# RelaySchema.net
KiCad netlist of a schematic drawn in Altium Designer
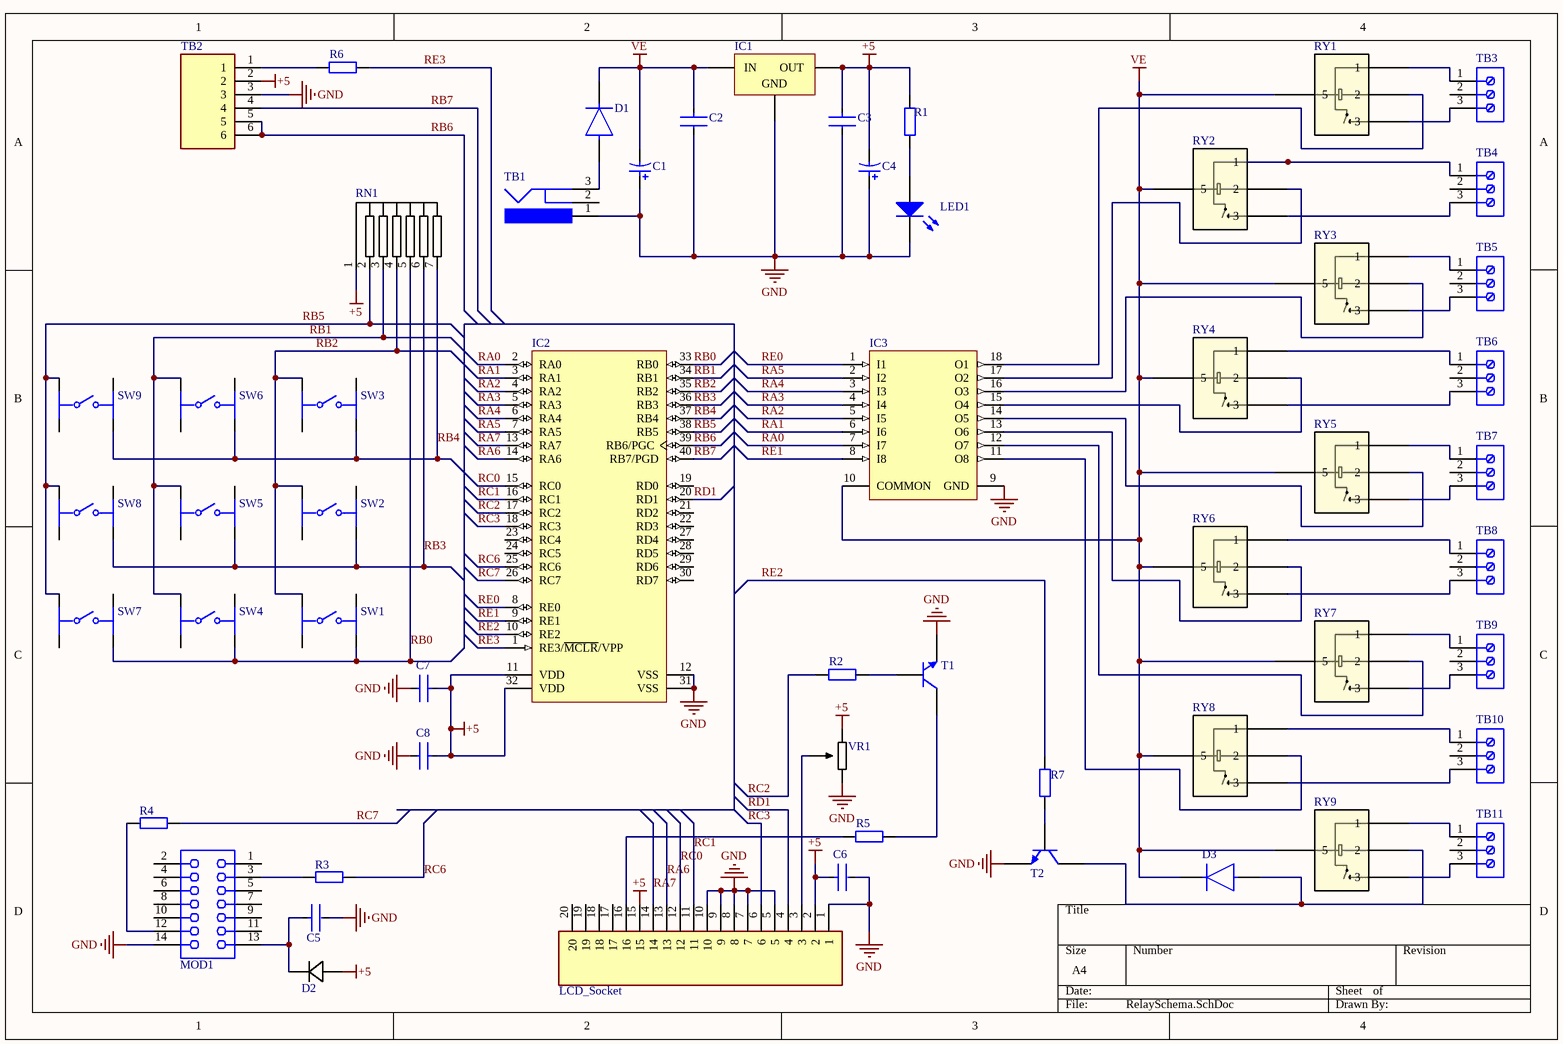
[diagram p0: RelaySchema.SchDoc]

(export (version "E")
  (design (tool "Eeschema 10.0.6"))
  (components
    (comp (ref "C1")
      (value "ECA-1HM221")
      (footprint "CAPPR65-500-1250X1000X1350")
      (description "Aluminum Electrolytic Capacitor, 220 uF, +/- 20%, 50 V, -40 to 85 degC, 2-Pin THD, RoHS, Bulk")
      (libsource (lib "Altium Content Vault") (part "CAP-P-2"))
    )
    (comp (ref "C2")
      (value "SR205C104KAR")
      (footprint "FP-SR20-MFG")
      (description "CAP CER 0.1UF 50V X7R RADIAL")
      (fields (field (name "VOLTAGE") "50V") (field (name "TOLERANCE") "10%"))
      (libsource (lib "Altium Content Vault") (part "11868f565c42a9108669ba33697ecf6"))
    )
    (comp (ref "C3")
      (value "SR205C104KAR")
      (footprint "FP-SR20-MFG")
      (description "CAP CER 0.1UF 50V X7R RADIAL")
      (fields (field (name "VOLTAGE") "50V") (field (name "TOLERANCE") "10%"))
      (libsource (lib "Altium Content Vault") (part "11868f565c42a9108669ba33697ecf6"))
    )
    (comp (ref "C4")
      (value "ECA1HM101")
      (footprint "CAPPR65-350-1150X800X1250")
      (description "Aluminum Electrolytic Capacitor, 100 uF, +/- 20%, 50 V, -40 to 85 degC, 2-Pin THD, RoHS, Bulk")
      (fields (field (name "MANUFACTURER") "Panasonic") (field (name "VOLTAGE") "50V"))
      (libsource (lib "Altium Content Vault") (part "CAP-P-2"))
    )
    (comp (ref "C5")
      (value "SR205C104KAR")
      (footprint "FP-SR20-MFG")
      (description "CAP CER 0.1UF 50V X7R RADIAL")
      (fields (field (name "VOLTAGE") "50V") (field (name "TOLERANCE") "10%"))
      (libsource (lib "Altium Content Vault") (part "11868f565c42a9108669ba33697ecf6"))
    )
    (comp (ref "C6")
      (value "SR205C104KAR")
      (footprint "FP-SR20-MFG")
      (description "CAP CER 0.1UF 50V X7R RADIAL")
      (fields (field (name "VOLTAGE") "50V") (field (name "TOLERANCE") "10%"))
      (libsource (lib "Altium Content Vault") (part "11868f565c42a9108669ba33697ecf6"))
    )
    (comp (ref "C7")
      (value "SR205C104KAR")
      (footprint "FP-SR20-MFG")
      (description "CAP CER 0.1UF 50V X7R RADIAL")
      (fields (field (name "VOLTAGE") "50V") (field (name "TOLERANCE") "10%"))
      (libsource (lib "Altium Content Vault") (part "11868f565c42a9108669ba33697ecf6"))
    )
    (comp (ref "C8")
      (value "SR205C104KAR")
      (footprint "FP-SR20-MFG")
      (description "CAP CER 0.1UF 50V X7R RADIAL")
      (fields (field (name "VOLTAGE") "50V") (field (name "TOLERANCE") "10%"))
      (libsource (lib "Altium Content Vault") (part "11868f565c42a9108669ba33697ecf6"))
    )
    (comp (ref "D1")
      (value "1N4007")
      (footprint "FP-1N4007-MFG")
      (description "Rectifier diode 1000 V 1 A DO-41, ,")
      (fields
        (field (name "MANUFACTURER") "Diotec")
        (field (name "OCTOPART") "https://octopart.com/1n4007-diotec-4040411")
      )
      (libsource (lib "Altium Content Vault") (part "d7152d700b627762746794eb795d46e"))
    )
    (comp (ref "D2")
      (value "BAT43")
      (footprint "DO-35_STM")
      (description "No Description Available")
      (fields (field (name "COPYRIGHT") "Copyright (C) 2018 Accelerated Designs. All rights reserved"))
      (libsource (lib "2021-03-09_13-20-37") (part "BAT43"))
    )
    (comp (ref "D3")
      (value "1N4007")
      (footprint "FP-1N4007-MFG")
      (description "Rectifier diode 1000 V 1 A DO-41, ,")
      (fields
        (field (name "MANUFACTURER") "Diotec")
        (field (name "OCTOPART") "https://octopart.com/1n4007-diotec-4040411")
      )
      (libsource (lib "Altium Content Vault") (part "d7152d700b627762746794eb795d46e"))
    )
    (comp (ref "IC1")
      (value "MC7805CTG")
      (footprint "ONSC-TO-220-3-221AB-01")
      (description "Positive Voltage Regulator, 1 A, 5 V, 0 to 125 degC, 3-Pin TO-220, RoHS, Tube")
      (fields (field (name "MANUFACTURER") "ON Semiconductor"))
      (libsource (lib "Altium Content Vault") (part "ONSC-MC7805CTG-TO-220-3"))
    )
    (comp (ref "IC2")
      (value "PIC18F45K22-E/P")
      (footprint "MCHP-PDIP-P40")
      (fields (field (name "MANUFACTURER") "Microchip"))
      (libsource (lib "Altium Content Vault") (part "MCHP-PIC18F4XK22-PDIP-40"))
    )
    (comp (ref "IC3")
      (value "ULN2803A")
      (footprint "STM-DIP-18")
      (description "Eight Darlington Arrays, 50 V, 2.25 W, 500 mA, 18-Pin DIP, RoHS, Tube")
      (fields (field (name "MANUFACTURER") "STMicroelectronics"))
      (libsource (lib "Altium Content Vault") (part "TOSH-ULN2803_04-DIP-18"))
    )
    (comp (ref "LCD_Socket")
      (value "D01-9972042")
      (footprint "SamacSys:D019972042")
      (description "Connector")
      (fields (field (name "MOUSER2 PART NUMBER") "855-D01-9972042"))
      (libsource (lib "*") (part "D01-9972042"))
    )
    (comp (ref "LED1")
      (value "151031SS04000")
      (footprint "Type 3mm")
      (description "THT LED round mono-color color lens, WL-TMRW, Super Red")
      (fields (field (name "MANUFACTURER") "Wuerth Elektronik"))
      (libsource (lib "Altium Content Vault") (part "WE-LED_K1A2-2"))
    )
    (comp (ref "MOD1")
      (value "ESQ-107-12-G-D")
      (footprint "DIP14")
      (fields (field (name "MANUFACTURER") "Samtec"))
      (libsource (lib "Relay") (part "CMP-1026-00022-1"))
    )
    (comp (ref "R1")
      (value "ERJ-8GEYJ331V")
      (footprint "RESC3216X70X50NL05T20")
      (fields (field (name "MANUFACTURER") "Panasonic"))
      (libsource (lib "") (part "RES_1"))
    )
    (comp (ref "R2")
      (value "ERJ-8GEYJ472V")
      (footprint "RESC3216X70X50LL05T20")
      (fields (field (name "MANUFACTURER") "Panasonic"))
      (libsource (lib "") (part "RES_3"))
    )
    (comp (ref "R3")
      (value "ERJ-8GEYJ102V")
      (footprint "RESC3216X70X50LL05T20")
      (fields (field (name "MANUFACTURER") "Panasonic"))
      (libsource (lib "Altium Content Vault") (part "RES"))
    )
    (comp (ref "R4")
      (value "ERJ-8GEYJ102V")
      (footprint "RESC3216X70X50LL05T20")
      (fields (field (name "MANUFACTURER") "Panasonic"))
      (libsource (lib "Altium Content Vault") (part "RES"))
    )
    (comp (ref "R5")
      (value "ERJ-8GEYJ4R7V")
      (footprint "RESC3216X70X50NL05T20")
      (fields (field (name "MANUFACTURER") "Panasonic"))
      (libsource (lib "Altium Content Vault") (part "RES"))
    )
    (comp (ref "R6")
      (value "ERJ-8GEYJ100V")
      (footprint "RESC3216X70X50LL05T20")
      (fields (field (name "MANUFACTURER") "Panasonic"))
      (libsource (lib "Altium Content Vault") (part "RES"))
    )
    (comp (ref "R7")
      (value "ERJ-8GEYJ472V")
      (footprint "RESC3216X70X50LL05T20")
      (fields (field (name "MANUFACTURER") "Panasonic"))
      (libsource (lib "") (part "RES_2"))
    )
    (comp (ref "RN1")
      (value "4607X-101-103LF")
      (footprint "BO_4607X")
      (description "No Description Available")
      (fields (field (name "COPYRIGHT") "Copyright (C) 2018 Accelerated Designs. All rights reserved"))
      (libsource (lib "RN1") (part "4607X-101-103LF"))
    )
    (comp (ref "RY1")
      (value "G5LE-1A-CF DC12")
      (footprint "RELAY_G5LE-1A DC5_OMR")
      (description "No Description Available")
      (fields (field (name "COPYRIGHT") "Copyright (C) 2018 Accelerated Designs. All rights reserved"))
      (libsource (lib "2021-03-09_14-09-04") (part "G5LE-1A-CF DC12"))
    )
    (comp (ref "RY2")
      (value "G5LE-1A-CF DC12")
      (footprint "RELAY_G5LE-1A DC5_OMR")
      (description "No Description Available")
      (fields (field (name "COPYRIGHT") "Copyright (C) 2018 Accelerated Designs. All rights reserved"))
      (libsource (lib "2021-03-09_14-09-04") (part "G5LE-1A-CF DC12"))
    )
    (comp (ref "RY3")
      (value "G5LE-1A-CF DC12")
      (footprint "RELAY_G5LE-1A DC5_OMR")
      (description "No Description Available")
      (fields (field (name "COPYRIGHT") "Copyright (C) 2018 Accelerated Designs. All rights reserved"))
      (libsource (lib "2021-03-09_14-09-04") (part "G5LE-1A-CF DC12"))
    )
    (comp (ref "RY4")
      (value "G5LE-1A-CF DC12")
      (footprint "RELAY_G5LE-1A DC5_OMR")
      (description "No Description Available")
      (fields (field (name "COPYRIGHT") "Copyright (C) 2018 Accelerated Designs. All rights reserved"))
      (libsource (lib "2021-03-09_14-09-04") (part "G5LE-1A-CF DC12"))
    )
    (comp (ref "RY5")
      (value "G5LE-1A-CF DC12")
      (footprint "RELAY_G5LE-1A DC5_OMR")
      (description "No Description Available")
      (fields (field (name "COPYRIGHT") "Copyright (C) 2018 Accelerated Designs. All rights reserved"))
      (libsource (lib "2021-03-09_14-09-04") (part "G5LE-1A-CF DC12"))
    )
    (comp (ref "RY6")
      (value "G5LE-1A-CF DC12")
      (footprint "RELAY_G5LE-1A DC5_OMR")
      (description "No Description Available")
      (fields (field (name "COPYRIGHT") "Copyright (C) 2018 Accelerated Designs. All rights reserved"))
      (libsource (lib "2021-03-09_14-09-04") (part "G5LE-1A-CF DC12"))
    )
    (comp (ref "RY7")
      (value "G5LE-1A-CF DC12")
      (footprint "RELAY_G5LE-1A DC5_OMR")
      (description "No Description Available")
      (fields (field (name "COPYRIGHT") "Copyright (C) 2018 Accelerated Designs. All rights reserved"))
      (libsource (lib "2021-03-09_14-09-04") (part "G5LE-1A-CF DC12"))
    )
    (comp (ref "RY8")
      (value "G5LE-1A-CF DC12")
      (footprint "RELAY_G5LE-1A DC5_OMR")
      (description "No Description Available")
      (fields (field (name "COPYRIGHT") "Copyright (C) 2018 Accelerated Designs. All rights reserved"))
      (libsource (lib "2021-03-09_14-09-04") (part "G5LE-1A-CF DC12"))
    )
    (comp (ref "RY9")
      (value "G5LE-1A-CF DC12")
      (footprint "RELAY_G5LE-1A DC5_OMR")
      (description "No Description Available")
      (fields (field (name "COPYRIGHT") "Copyright (C) 2018 Accelerated Designs. All rights reserved"))
      (libsource (lib "2021-03-09_14-09-04") (part "G5LE-1A-CF DC12"))
    )
    (comp (ref "SW1")
      (value "B3F-4000")
      (footprint "FP-B3F-4000-MFG")
      (description "SWITCH TACTILE SPST-NO 0.05A 24V")
      (fields
        (field (name "MANUFACTURER") "Omron")
        (field (name "OCTOPART") "https://octopart.com/b3f-4000-omron-22510")
      )
      (libsource (lib "Altium Content Vault") (part "b8895f3f4cefb76e1819d2863dba89b"))
    )
    (comp (ref "SW2")
      (value "B3F-4000")
      (footprint "FP-B3F-4000-MFG")
      (description "SWITCH TACTILE SPST-NO 0.05A 24V")
      (fields
        (field (name "MANUFACTURER") "Omron")
        (field (name "OCTOPART") "https://octopart.com/b3f-4000-omron-22510")
      )
      (libsource (lib "Altium Content Vault") (part "b8895f3f4cefb76e1819d2863dba89b"))
    )
    (comp (ref "SW3")
      (value "B3F-4000")
      (footprint "FP-B3F-4000-MFG")
      (description "SWITCH TACTILE SPST-NO 0.05A 24V")
      (fields
        (field (name "MANUFACTURER") "Omron")
        (field (name "OCTOPART") "https://octopart.com/b3f-4000-omron-22510")
      )
      (libsource (lib "Altium Content Vault") (part "b8895f3f4cefb76e1819d2863dba89b"))
    )
    (comp (ref "SW4")
      (value "B3F-4000")
      (footprint "FP-B3F-4000-MFG")
      (description "SWITCH TACTILE SPST-NO 0.05A 24V")
      (fields
        (field (name "MANUFACTURER") "Omron")
        (field (name "OCTOPART") "https://octopart.com/b3f-4000-omron-22510")
      )
      (libsource (lib "Altium Content Vault") (part "b8895f3f4cefb76e1819d2863dba89b"))
    )
    (comp (ref "SW5")
      (value "B3F-4000")
      (footprint "FP-B3F-4000-MFG")
      (description "SWITCH TACTILE SPST-NO 0.05A 24V")
      (fields
        (field (name "MANUFACTURER") "Omron")
        (field (name "OCTOPART") "https://octopart.com/b3f-4000-omron-22510")
      )
      (libsource (lib "Altium Content Vault") (part "b8895f3f4cefb76e1819d2863dba89b"))
    )
    (comp (ref "SW6")
      (value "B3F-4000")
      (footprint "FP-B3F-4000-MFG")
      (description "SWITCH TACTILE SPST-NO 0.05A 24V")
      (fields
        (field (name "MANUFACTURER") "Omron")
        (field (name "OCTOPART") "https://octopart.com/b3f-4000-omron-22510")
      )
      (libsource (lib "Altium Content Vault") (part "b8895f3f4cefb76e1819d2863dba89b"))
    )
    (comp (ref "SW7")
      (value "B3F-4000")
      (footprint "FP-B3F-4000-MFG")
      (description "SWITCH TACTILE SPST-NO 0.05A 24V")
      (fields
        (field (name "MANUFACTURER") "Omron")
        (field (name "OCTOPART") "https://octopart.com/b3f-4000-omron-22510")
      )
      (libsource (lib "Altium Content Vault") (part "b8895f3f4cefb76e1819d2863dba89b"))
    )
    (comp (ref "SW8")
      (value "B3F-4000")
      (footprint "FP-B3F-4000-MFG")
      (description "SWITCH TACTILE SPST-NO 0.05A 24V")
      (fields
        (field (name "MANUFACTURER") "Omron")
        (field (name "OCTOPART") "https://octopart.com/b3f-4000-omron-22510")
      )
      (libsource (lib "Altium Content Vault") (part "b8895f3f4cefb76e1819d2863dba89b"))
    )
    (comp (ref "SW9")
      (value "B3F-4000")
      (footprint "FP-B3F-4000-MFG")
      (description "SWITCH TACTILE SPST-NO 0.05A 24V")
      (fields
        (field (name "MANUFACTURER") "Omron")
        (field (name "OCTOPART") "https://octopart.com/b3f-4000-omron-22510")
      )
      (libsource (lib "Altium Content Vault") (part "b8895f3f4cefb76e1819d2863dba89b"))
    )
    (comp (ref "T1")
      (value "BC546BRL1G")
      (footprint "ONSC-TO-92-3-29-11_AM_BL")
      (description "Amplifier Transistor, NPN Silicon, 3-Pin TO-92, Pb-Free, Tape and Reel")
      (fields (field (name "MANUFACTURER") "On Semiconductor"))
      (libsource (lib "Altium Content Vault") (part "ONSC-NPN-C1B2E3-3"))
    )
    (comp (ref "T2")
      (value "BC546BRL1G")
      (footprint "ONSC-TO-92-3-29-11_AM_BL")
      (description "Amplifier Transistor, NPN Silicon, 3-Pin TO-92, Pb-Free, Tape and Reel")
      (fields (field (name "MANUFACTURER") "On Semiconductor"))
      (libsource (lib "Altium Content Vault") (part "ONSC-NPN-C1B2E3-3"))
    )
    (comp (ref "TB1") (value "TB1") (footprint "MJ-180PH") (libsource (lib "Schlib1") (part "TB1")))
    (comp (ref "TB2")
      (value "M20-7820646")
      (footprint "SamacSys:HDRV6W70P0X254_1X6_1564X250X865P")
      (description "Connector")
      (fields (field (name "MOUSER2 PART NUMBER") "855-M20-7820646"))
      (libsource (lib "*") (part "M20-7820646"))
    )
    (comp (ref "TB3")
      (value "691101710003")
      (footprint "691101710003")
      (description "Series 101 - 5.00 mm Horizontal Entry Modular with Pressure Clamp WR-TBL, 3 pin")
      (fields (field (name "MANUFACTURER") "Wurth Elektronik") (field (name "PUBLISHER") "WurthElektronik"))
      (libsource (lib "Altium Content Vault") (part "WE-CN-1P-F-TB3"))
    )
    (comp (ref "TB4")
      (value "691101710003")
      (footprint "691101710003")
      (description "Series 101 - 5.00 mm Horizontal Entry Modular with Pressure Clamp WR-TBL, 3 pin")
      (fields (field (name "MANUFACTURER") "Wurth Elektronik") (field (name "PUBLISHER") "WurthElektronik"))
      (libsource (lib "Altium Content Vault") (part "WE-CN-1P-F-TB3"))
    )
    (comp (ref "TB5")
      (value "691101710003")
      (footprint "691101710003")
      (description "Series 101 - 5.00 mm Horizontal Entry Modular with Pressure Clamp WR-TBL, 3 pin")
      (fields (field (name "MANUFACTURER") "Wurth Elektronik") (field (name "PUBLISHER") "WurthElektronik"))
      (libsource (lib "Altium Content Vault") (part "WE-CN-1P-F-TB3"))
    )
    (comp (ref "TB6")
      (value "691101710003")
      (footprint "691101710003")
      (description "Series 101 - 5.00 mm Horizontal Entry Modular with Pressure Clamp WR-TBL, 3 pin")
      (fields (field (name "MANUFACTURER") "Wurth Elektronik") (field (name "PUBLISHER") "WurthElektronik"))
      (libsource (lib "Altium Content Vault") (part "WE-CN-1P-F-TB3"))
    )
    (comp (ref "TB7")
      (value "691101710003")
      (footprint "691101710003")
      (description "Series 101 - 5.00 mm Horizontal Entry Modular with Pressure Clamp WR-TBL, 3 pin")
      (fields (field (name "MANUFACTURER") "Wurth Elektronik") (field (name "PUBLISHER") "WurthElektronik"))
      (libsource (lib "Altium Content Vault") (part "WE-CN-1P-F-TB3"))
    )
    (comp (ref "TB8")
      (value "691101710003")
      (footprint "691101710003")
      (description "Series 101 - 5.00 mm Horizontal Entry Modular with Pressure Clamp WR-TBL, 3 pin")
      (fields (field (name "MANUFACTURER") "Wurth Elektronik") (field (name "PUBLISHER") "WurthElektronik"))
      (libsource (lib "Altium Content Vault") (part "WE-CN-1P-F-TB3"))
    )
    (comp (ref "TB9")
      (value "691101710003")
      (footprint "691101710003")
      (description "Series 101 - 5.00 mm Horizontal Entry Modular with Pressure Clamp WR-TBL, 3 pin")
      (fields (field (name "MANUFACTURER") "Wurth Elektronik") (field (name "PUBLISHER") "WurthElektronik"))
      (libsource (lib "Altium Content Vault") (part "WE-CN-1P-F-TB3"))
    )
    (comp (ref "TB10")
      (value "691101710003")
      (footprint "691101710003")
      (description "Series 101 - 5.00 mm Horizontal Entry Modular with Pressure Clamp WR-TBL, 3 pin")
      (fields (field (name "MANUFACTURER") "Wurth Elektronik") (field (name "PUBLISHER") "WurthElektronik"))
      (libsource (lib "Altium Content Vault") (part "WE-CN-1P-F-TB3"))
    )
    (comp (ref "TB11")
      (value "691101710003")
      (footprint "691101710003")
      (description "Series 101 - 5.00 mm Horizontal Entry Modular with Pressure Clamp WR-TBL, 3 pin")
      (fields (field (name "MANUFACTURER") "Wurth Elektronik") (field (name "PUBLISHER") "WurthElektronik"))
      (libsource (lib "Altium Content Vault") (part "WE-CN-1P-F-TB3"))
    )
    (comp (ref "VR1")
      (value "3362P-1-103LF")
      (footprint "BOUR-3362P")
      (description "Square Trimpot(R) Trimming Potentiometer, 10 KOhm, 300 V, -55 to 125 degC, 3-Pin THD, RoHS, Tube")
      (fields (field (name "TOLERANCE") "1%") (field (name "MANUFACTURER") "Bourns"))
      (libsource (lib "RN1") (part "CMP-1747-00004-1"))
    )
  )
  (nets
    (net (code "1") (name "+5") (class "Default")
      (node (ref "C3") (pin "1") (pinfunction "1_1") (pintype "passive"))
      (node (ref "C4") (pin "2") (pinfunction "2_2") (pintype "passive"))
      (node (ref "C6") (pin "1") (pinfunction "1_1") (pintype "passive"))
      (node (ref "C7") (pin "1") (pinfunction "1_1") (pintype "passive"))
      (node (ref "C8") (pin "1") (pinfunction "1_1") (pintype "passive"))
      (node (ref "D2") (pin "1") (pinfunction "1_1") (pintype "passive"))
      (node (ref "IC1") (pin "3") (pinfunction "OUT_3") (pintype "power_in"))
      (node (ref "IC2") (pin "11") (pinfunction "VDD_11") (pintype "power_in"))
      (node (ref "IC2") (pin "32") (pinfunction "VDD_32") (pintype "power_in"))
      (node (ref "LCD_Socket") (pin "15") (pinfunction "15_15") (pintype "passive"))
      (node (ref "LCD_Socket") (pin "2") (pinfunction "2_2") (pintype "passive"))
      (node (ref "R1") (pin "2") (pinfunction "2_2") (pintype "passive"))
      (node (ref "RN1") (pin "1") (pinfunction "1_1") (pintype "passive"))
      (node (ref "TB2") (pin "2") (pinfunction "2_2") (pintype "passive"))
      (node (ref "VR1") (pin "1") (pinfunction "CCW_1") (pintype "passive"))
    )
    (net (code "2") (name "/RA0") (class "Default")
      (node (ref "IC2") (pin "2") (pinfunction "RA0_2") (pintype "bidirectional"))
      (node (ref "IC3") (pin "7") (pinfunction "I7_7") (pintype "input"))
    )
    (net (code "3") (name "/RA1") (class "Default")
      (node (ref "IC2") (pin "3") (pinfunction "RA1_3") (pintype "bidirectional"))
      (node (ref "IC3") (pin "6") (pinfunction "I6_6") (pintype "input"))
    )
    (net (code "4") (name "/RA2") (class "Default")
      (node (ref "IC2") (pin "4") (pinfunction "RA2_4") (pintype "bidirectional"))
      (node (ref "IC3") (pin "5") (pinfunction "I5_5") (pintype "input"))
    )
    (net (code "5") (name "/RA3") (class "Default")
      (node (ref "IC2") (pin "5") (pinfunction "RA3_5") (pintype "bidirectional"))
      (node (ref "IC3") (pin "4") (pinfunction "I4_4") (pintype "input"))
    )
    (net (code "6") (name "/RA4") (class "Default")
      (node (ref "IC2") (pin "6") (pinfunction "RA4_6") (pintype "bidirectional"))
      (node (ref "IC3") (pin "3") (pinfunction "I3_3") (pintype "input"))
    )
    (net (code "7") (name "/RA5") (class "Default")
      (node (ref "IC2") (pin "7") (pinfunction "RA5_7") (pintype "bidirectional"))
      (node (ref "IC3") (pin "2") (pinfunction "I2_2") (pintype "input"))
    )
    (net (code "8") (name "/RA6") (class "Default")
      (node (ref "IC2") (pin "14") (pinfunction "RA6_14") (pintype "bidirectional"))
      (node (ref "LCD_Socket") (pin "13") (pinfunction "13_13") (pintype "passive"))
    )
    (net (code "9") (name "/RA7") (class "Default")
      (node (ref "IC2") (pin "13") (pinfunction "RA7_13") (pintype "bidirectional"))
      (node (ref "LCD_Socket") (pin "14") (pinfunction "14_14") (pintype "passive"))
    )
    (net (code "10") (name "/RB0") (class "Default")
      (node (ref "IC2") (pin "33") (pinfunction "RB0_33") (pintype "bidirectional"))
      (node (ref "RN1") (pin "5") (pinfunction "5_5") (pintype "passive"))
      (node (ref "SW1") (pin "4") (pinfunction "4_4") (pintype "passive"))
      (node (ref "SW4") (pin "4") (pinfunction "4_4") (pintype "passive"))
      (node (ref "SW7") (pin "4") (pinfunction "4_4") (pintype "passive"))
    )
    (net (code "11") (name "/RB1") (class "Default")
      (node (ref "IC2") (pin "34") (pinfunction "RB1_34") (pintype "bidirectional"))
      (node (ref "RN1") (pin "3") (pinfunction "3_3") (pintype "passive"))
      (node (ref "SW4") (pin "1") (pinfunction "1_1") (pintype "passive"))
      (node (ref "SW5") (pin "1") (pinfunction "1_1") (pintype "passive"))
      (node (ref "SW6") (pin "1") (pinfunction "1_1") (pintype "passive"))
    )
    (net (code "12") (name "/RB2") (class "Default")
      (node (ref "IC2") (pin "35") (pinfunction "RB2_35") (pintype "bidirectional"))
      (node (ref "RN1") (pin "4") (pinfunction "4_4") (pintype "passive"))
      (node (ref "SW1") (pin "1") (pinfunction "1_1") (pintype "passive"))
      (node (ref "SW2") (pin "1") (pinfunction "1_1") (pintype "passive"))
      (node (ref "SW3") (pin "1") (pinfunction "1_1") (pintype "passive"))
    )
    (net (code "13") (name "/RB3") (class "Default")
      (node (ref "IC2") (pin "36") (pinfunction "RB3_36") (pintype "bidirectional"))
      (node (ref "RN1") (pin "6") (pinfunction "6_6") (pintype "passive"))
      (node (ref "SW2") (pin "4") (pinfunction "4_4") (pintype "passive"))
      (node (ref "SW5") (pin "4") (pinfunction "4_4") (pintype "passive"))
      (node (ref "SW8") (pin "4") (pinfunction "4_4") (pintype "passive"))
    )
    (net (code "14") (name "/RB4") (class "Default")
      (node (ref "IC2") (pin "37") (pinfunction "RB4_37") (pintype "bidirectional"))
      (node (ref "RN1") (pin "7") (pinfunction "7_7") (pintype "passive"))
      (node (ref "SW3") (pin "4") (pinfunction "4_4") (pintype "passive"))
      (node (ref "SW6") (pin "4") (pinfunction "4_4") (pintype "passive"))
      (node (ref "SW9") (pin "4") (pinfunction "4_4") (pintype "passive"))
    )
    (net (code "15") (name "/RB5") (class "Default")
      (node (ref "IC2") (pin "38") (pinfunction "RB5_38") (pintype "bidirectional"))
      (node (ref "RN1") (pin "2") (pinfunction "2_2") (pintype "passive"))
      (node (ref "SW7") (pin "1") (pinfunction "1_1") (pintype "passive"))
      (node (ref "SW8") (pin "1") (pinfunction "1_1") (pintype "passive"))
      (node (ref "SW9") (pin "1") (pinfunction "1_1") (pintype "passive"))
    )
    (net (code "16") (name "/RB6") (class "Default")
      (node (ref "IC2") (pin "39") (pinfunction "RB6/PGC_39") (pintype "bidirectional"))
      (node (ref "TB2") (pin "5") (pinfunction "5_5") (pintype "passive"))
      (node (ref "TB2") (pin "6") (pinfunction "6_6") (pintype "passive"))
    )
    (net (code "17") (name "/RB7") (class "Default")
      (node (ref "IC2") (pin "40") (pinfunction "RB7/PGD_40") (pintype "bidirectional"))
      (node (ref "TB2") (pin "4") (pinfunction "4_4") (pintype "passive"))
    )
    (net (code "18") (name "/RC0") (class "Default")
      (node (ref "IC2") (pin "15") (pinfunction "RC0_15") (pintype "bidirectional"))
      (node (ref "LCD_Socket") (pin "12") (pinfunction "12_12") (pintype "passive"))
    )
    (net (code "19") (name "/RC1") (class "Default")
      (node (ref "IC2") (pin "16") (pinfunction "RC1_16") (pintype "bidirectional"))
      (node (ref "LCD_Socket") (pin "11") (pinfunction "11_11") (pintype "passive"))
    )
    (net (code "20") (name "/RC2") (class "Default")
      (node (ref "IC2") (pin "17") (pinfunction "RC2_17") (pintype "bidirectional"))
      (node (ref "R2") (pin "2") (pinfunction "2_2") (pintype "passive"))
    )
    (net (code "21") (name "/RC3") (class "Default")
      (node (ref "IC2") (pin "18") (pinfunction "RC3_18") (pintype "bidirectional"))
      (node (ref "LCD_Socket") (pin "6") (pinfunction "6_6") (pintype "passive"))
    )
    (net (code "22") (name "/RC6") (class "Default")
      (node (ref "IC2") (pin "25") (pinfunction "RC6_25") (pintype "bidirectional"))
      (node (ref "R3") (pin "2") (pinfunction "2_2") (pintype "passive"))
    )
    (net (code "23") (name "/RC7") (class "Default")
      (node (ref "IC2") (pin "26") (pinfunction "RC7_26") (pintype "bidirectional"))
      (node (ref "R4") (pin "2") (pinfunction "2_2") (pintype "passive"))
    )
    (net (code "24") (name "/RD1") (class "Default")
      (node (ref "IC2") (pin "20") (pinfunction "RD1_20") (pintype "bidirectional"))
      (node (ref "LCD_Socket") (pin "4") (pinfunction "4_4") (pintype "passive"))
    )
    (net (code "25") (name "/RE0") (class "Default")
      (node (ref "IC2") (pin "8") (pinfunction "RE0_8") (pintype "bidirectional"))
      (node (ref "IC3") (pin "1") (pinfunction "I1_1") (pintype "input"))
    )
    (net (code "26") (name "/RE1") (class "Default")
      (node (ref "IC2") (pin "9") (pinfunction "RE1_9") (pintype "bidirectional"))
      (node (ref "IC3") (pin "8") (pinfunction "I8_8") (pintype "input"))
    )
    (net (code "27") (name "/RE2") (class "Default")
      (node (ref "IC2") (pin "10") (pinfunction "RE2_10") (pintype "bidirectional"))
      (node (ref "R7") (pin "1") (pinfunction "1_1") (pintype "passive"))
    )
    (net (code "28") (name "/RE3") (class "Default")
      (node (ref "IC2") (pin "1") (pinfunction "RE3/~{MCLR}/VPP_1") (pintype "input"))
      (node (ref "R6") (pin "2") (pinfunction "2_2") (pintype "passive"))
    )
    (net (code "29") (name "GND") (class "Default")
      (node (ref "C1") (pin "1") (pinfunction "1_1") (pintype "passive"))
      (node (ref "C2") (pin "2") (pinfunction "2_2") (pintype "passive"))
      (node (ref "C3") (pin "2") (pinfunction "2_2") (pintype "passive"))
      (node (ref "C4") (pin "1") (pinfunction "1_1") (pintype "passive"))
      (node (ref "C5") (pin "2") (pinfunction "2_2") (pintype "passive"))
      (node (ref "C6") (pin "2") (pinfunction "2_2") (pintype "passive"))
      (node (ref "C7") (pin "2") (pinfunction "2_2") (pintype "passive"))
      (node (ref "C8") (pin "2") (pinfunction "2_2") (pintype "passive"))
      (node (ref "IC1") (pin "2") (pinfunction "GND_2") (pintype "power_in"))
      (node (ref "IC2") (pin "12") (pinfunction "VSS_12") (pintype "power_in"))
      (node (ref "IC2") (pin "31") (pinfunction "VSS_31") (pintype "power_in"))
      (node (ref "IC3") (pin "9") (pinfunction "GND_9") (pintype "power_in"))
      (node (ref "LCD_Socket") (pin "1") (pinfunction "1_1") (pintype "passive"))
      (node (ref "LCD_Socket") (pin "10") (pinfunction "10_10") (pintype "passive"))
      (node (ref "LCD_Socket") (pin "5") (pinfunction "5_5") (pintype "passive"))
      (node (ref "LCD_Socket") (pin "7") (pinfunction "7_7") (pintype "passive"))
      (node (ref "LCD_Socket") (pin "8") (pinfunction "8_8") (pintype "passive"))
      (node (ref "LCD_Socket") (pin "9") (pinfunction "9_9") (pintype "passive"))
      (node (ref "LED1") (pin "1") (pinfunction "K_1") (pintype "passive"))
      (node (ref "MOD1") (pin "14") (pinfunction "14_14") (pintype "passive"))
      (node (ref "T1") (pin "3") (pinfunction "E_3") (pintype "passive"))
      (node (ref "T2") (pin "3") (pinfunction "E_3") (pintype "passive"))
      (node (ref "TB1") (pin "1") (pinfunction "1_1") (pintype "passive"))
      (node (ref "TB2") (pin "3") (pinfunction "3_3") (pintype "passive"))
      (node (ref "VR1") (pin "3") (pinfunction "CW_3") (pintype "passive"))
    )
    (net (code "30") (name "Net-(C5-Pad1)") (class "Default")
      (node (ref "C5") (pin "1") (pinfunction "1_1") (pintype "passive"))
      (node (ref "D2") (pin "2") (pinfunction "2_2") (pintype "passive"))
      (node (ref "MOD1") (pin "13") (pinfunction "13_13") (pintype "passive"))
    )
    (net (code "31") (name "Net-(D1-A)") (class "Default")
      (node (ref "D1") (pin "2") (pinfunction "A_2") (pintype "passive"))
      (node (ref "TB1") (pin "3") (pinfunction "3_3") (pintype "passive"))
    )
    (net (code "32") (name "Net-(D3-A)") (class "Default")
      (node (ref "D3") (pin "2") (pinfunction "A_2") (pintype "passive"))
      (node (ref "RY9") (pin "2") (pinfunction "2_2") (pintype "passive"))
      (node (ref "T2") (pin "1") (pinfunction "C_1") (pintype "passive"))
    )
    (net (code "33") (name "Net-(IC3-O1)") (class "Default")
      (node (ref "IC3") (pin "18") (pinfunction "O1_18") (pintype "output"))
      (node (ref "RY1") (pin "2") (pinfunction "2_2") (pintype "passive"))
    )
    (net (code "34") (name "Net-(IC3-O2)") (class "Default")
      (node (ref "IC3") (pin "17") (pinfunction "O2_17") (pintype "output"))
      (node (ref "RY2") (pin "2") (pinfunction "2_2") (pintype "passive"))
    )
    (net (code "35") (name "Net-(IC3-O3)") (class "Default")
      (node (ref "IC3") (pin "16") (pinfunction "O3_16") (pintype "output"))
      (node (ref "RY3") (pin "2") (pinfunction "2_2") (pintype "passive"))
    )
    (net (code "36") (name "Net-(IC3-O4)") (class "Default")
      (node (ref "IC3") (pin "15") (pinfunction "O4_15") (pintype "output"))
      (node (ref "RY4") (pin "2") (pinfunction "2_2") (pintype "passive"))
    )
    (net (code "37") (name "Net-(IC3-O5)") (class "Default")
      (node (ref "IC3") (pin "14") (pinfunction "O5_14") (pintype "output"))
      (node (ref "RY5") (pin "2") (pinfunction "2_2") (pintype "passive"))
    )
    (net (code "38") (name "Net-(IC3-O6)") (class "Default")
      (node (ref "IC3") (pin "13") (pinfunction "O6_13") (pintype "output"))
      (node (ref "RY6") (pin "2") (pinfunction "2_2") (pintype "passive"))
    )
    (net (code "39") (name "Net-(IC3-O7)") (class "Default")
      (node (ref "IC3") (pin "12") (pinfunction "O7_12") (pintype "output"))
      (node (ref "RY7") (pin "2") (pinfunction "2_2") (pintype "passive"))
    )
    (net (code "40") (name "Net-(IC3-O8)") (class "Default")
      (node (ref "IC3") (pin "11") (pinfunction "O8_11") (pintype "output"))
      (node (ref "RY8") (pin "2") (pinfunction "2_2") (pintype "passive"))
    )
    (net (code "41") (name "Net-(LCD_Socket-Pad16)") (class "Default")
      (node (ref "LCD_Socket") (pin "16") (pinfunction "16_16") (pintype "passive"))
      (node (ref "R5") (pin "1") (pinfunction "1_1") (pintype "passive"))
    )
    (net (code "42") (name "Net-(LED1-A)") (class "Default")
      (node (ref "LED1") (pin "2") (pinfunction "A_2") (pintype "passive"))
      (node (ref "R1") (pin "1") (pinfunction "1_1") (pintype "passive"))
    )
    (net (code "43") (name "Net-(MOD1-Pad3)") (class "Default")
      (node (ref "MOD1") (pin "3") (pinfunction "3_3") (pintype "passive"))
      (node (ref "R3") (pin "1") (pinfunction "1_1") (pintype "passive"))
    )
    (net (code "44") (name "Net-(MOD1-Pad12)") (class "Default")
      (node (ref "MOD1") (pin "12") (pinfunction "12_12") (pintype "passive"))
      (node (ref "R4") (pin "1") (pinfunction "1_1") (pintype "passive"))
    )
    (net (code "45") (name "Net-(R6-Pad1)") (class "Default")
      (node (ref "R6") (pin "1") (pinfunction "1_1") (pintype "passive"))
      (node (ref "TB2") (pin "1") (pinfunction "1_1") (pintype "passive"))
    )
    (net (code "46") (name "Net-(RY1-Pad1)") (class "Default")
      (node (ref "RY1") (pin "1") (pinfunction "1_1") (pintype "passive"))
      (node (ref "TB3") (pin "1") (pinfunction "1_1") (pintype "passive"))
    )
    (net (code "47") (name "Net-(RY1-Pad3)") (class "Default")
      (node (ref "RY1") (pin "3") (pinfunction "3_3") (pintype "passive"))
      (node (ref "TB3") (pin "3") (pinfunction "3_3") (pintype "passive"))
    )
    (net (code "48") (name "Net-(RY2-Pad1)") (class "Default")
      (node (ref "RY2") (pin "1") (pinfunction "1_1") (pintype "passive"))
      (node (ref "TB4") (pin "1") (pinfunction "1_1") (pintype "passive"))
    )
    (net (code "49") (name "Net-(RY2-Pad3)") (class "Default")
      (node (ref "RY2") (pin "3") (pinfunction "3_3") (pintype "passive"))
      (node (ref "TB4") (pin "3") (pinfunction "3_3") (pintype "passive"))
    )
    (net (code "50") (name "Net-(RY3-Pad1)") (class "Default")
      (node (ref "RY3") (pin "1") (pinfunction "1_1") (pintype "passive"))
      (node (ref "TB5") (pin "1") (pinfunction "1_1") (pintype "passive"))
    )
    (net (code "51") (name "Net-(RY3-Pad3)") (class "Default")
      (node (ref "RY3") (pin "3") (pinfunction "3_3") (pintype "passive"))
      (node (ref "TB5") (pin "3") (pinfunction "3_3") (pintype "passive"))
    )
    (net (code "52") (name "Net-(RY4-Pad1)") (class "Default")
      (node (ref "RY4") (pin "1") (pinfunction "1_1") (pintype "passive"))
      (node (ref "TB6") (pin "1") (pinfunction "1_1") (pintype "passive"))
    )
    (net (code "53") (name "Net-(RY4-Pad3)") (class "Default")
      (node (ref "RY4") (pin "3") (pinfunction "3_3") (pintype "passive"))
      (node (ref "TB6") (pin "3") (pinfunction "3_3") (pintype "passive"))
    )
    (net (code "54") (name "Net-(RY5-Pad1)") (class "Default")
      (node (ref "RY5") (pin "1") (pinfunction "1_1") (pintype "passive"))
      (node (ref "TB7") (pin "1") (pinfunction "1_1") (pintype "passive"))
    )
    (net (code "55") (name "Net-(RY5-Pad3)") (class "Default")
      (node (ref "RY5") (pin "3") (pinfunction "3_3") (pintype "passive"))
      (node (ref "TB7") (pin "3") (pinfunction "3_3") (pintype "passive"))
    )
    (net (code "56") (name "Net-(RY6-Pad1)") (class "Default")
      (node (ref "RY6") (pin "1") (pinfunction "1_1") (pintype "passive"))
      (node (ref "TB8") (pin "1") (pinfunction "1_1") (pintype "passive"))
    )
    (net (code "57") (name "Net-(RY6-Pad3)") (class "Default")
      (node (ref "RY6") (pin "3") (pinfunction "3_3") (pintype "passive"))
      (node (ref "TB8") (pin "3") (pinfunction "3_3") (pintype "passive"))
    )
    (net (code "58") (name "Net-(RY7-Pad1)") (class "Default")
      (node (ref "RY7") (pin "1") (pinfunction "1_1") (pintype "passive"))
      (node (ref "TB9") (pin "1") (pinfunction "1_1") (pintype "passive"))
    )
    (net (code "59") (name "Net-(RY7-Pad3)") (class "Default")
      (node (ref "RY7") (pin "3") (pinfunction "3_3") (pintype "passive"))
      (node (ref "TB9") (pin "3") (pinfunction "3_3") (pintype "passive"))
    )
    (net (code "60") (name "Net-(RY8-Pad1)") (class "Default")
      (node (ref "RY8") (pin "1") (pinfunction "1_1") (pintype "passive"))
      (node (ref "TB10") (pin "1") (pinfunction "1_1") (pintype "passive"))
    )
    (net (code "61") (name "Net-(RY8-Pad3)") (class "Default")
      (node (ref "RY8") (pin "3") (pinfunction "3_3") (pintype "passive"))
      (node (ref "TB10") (pin "3") (pinfunction "3_3") (pintype "passive"))
    )
    (net (code "62") (name "Net-(RY9-Pad1)") (class "Default")
      (node (ref "RY9") (pin "1") (pinfunction "1_1") (pintype "passive"))
      (node (ref "TB11") (pin "1") (pinfunction "1_1") (pintype "passive"))
    )
    (net (code "63") (name "Net-(RY9-Pad3)") (class "Default")
      (node (ref "RY9") (pin "3") (pinfunction "3_3") (pintype "passive"))
      (node (ref "TB11") (pin "3") (pinfunction "3_3") (pintype "passive"))
    )
    (net (code "64") (name "Net-(T1-B)") (class "Default")
      (node (ref "R2") (pin "1") (pinfunction "1_1") (pintype "passive"))
      (node (ref "T1") (pin "2") (pinfunction "B_2") (pintype "passive"))
    )
    (net (code "65") (name "Net-(T1-C)") (class "Default")
      (node (ref "R5") (pin "2") (pinfunction "2_2") (pintype "passive"))
      (node (ref "T1") (pin "1") (pinfunction "C_1") (pintype "passive"))
    )
    (net (code "66") (name "Net-(T2-B)") (class "Default")
      (node (ref "R7") (pin "2") (pinfunction "2_2") (pintype "passive"))
      (node (ref "T2") (pin "2") (pinfunction "B_2") (pintype "passive"))
    )
    (net (code "67") (name "Net-(VR1-S)") (class "Default")
      (node (ref "LCD_Socket") (pin "3") (pinfunction "3_3") (pintype "passive"))
      (node (ref "VR1") (pin "2") (pinfunction "S_2") (pintype "passive"))
    )
    (net (code "68") (name "VE") (class "Default")
      (node (ref "C1") (pin "2") (pinfunction "2_2") (pintype "passive"))
      (node (ref "C2") (pin "1") (pinfunction "1_1") (pintype "passive"))
      (node (ref "D1") (pin "1") (pinfunction "C_1") (pintype "passive"))
      (node (ref "D3") (pin "1") (pinfunction "C_1") (pintype "passive"))
      (node (ref "IC1") (pin "1") (pinfunction "IN_1") (pintype "power_in"))
      (node (ref "IC3") (pin "10") (pinfunction "COMMON_10") (pintype "passive"))
      (node (ref "RY1") (pin "5") (pinfunction "5_5") (pintype "passive"))
      (node (ref "RY2") (pin "5") (pinfunction "5_5") (pintype "passive"))
      (node (ref "RY3") (pin "5") (pinfunction "5_5") (pintype "passive"))
      (node (ref "RY4") (pin "5") (pinfunction "5_5") (pintype "passive"))
      (node (ref "RY5") (pin "5") (pinfunction "5_5") (pintype "passive"))
      (node (ref "RY6") (pin "5") (pinfunction "5_5") (pintype "passive"))
      (node (ref "RY7") (pin "5") (pinfunction "5_5") (pintype "passive"))
      (node (ref "RY8") (pin "5") (pinfunction "5_5") (pintype "passive"))
      (node (ref "RY9") (pin "5") (pinfunction "5_5") (pintype "passive"))
    )
    (net (code "69") (name "unconnected-(IC2-RC4-Pad23)") (class "Default")
      (node (ref "IC2") (pin "23") (pinfunction "RC4_23") (pintype "bidirectional"))
    )
    (net (code "70") (name "unconnected-(IC2-RC5-Pad24)") (class "Default")
      (node (ref "IC2") (pin "24") (pinfunction "RC5_24") (pintype "bidirectional"))
    )
    (net (code "71") (name "unconnected-(IC2-RD0-Pad19)") (class "Default")
      (node (ref "IC2") (pin "19") (pinfunction "RD0_19") (pintype "bidirectional"))
    )
    (net (code "72") (name "unconnected-(IC2-RD2-Pad21)") (class "Default")
      (node (ref "IC2") (pin "21") (pinfunction "RD2_21") (pintype "bidirectional"))
    )
    (net (code "73") (name "unconnected-(IC2-RD3-Pad22)") (class "Default")
      (node (ref "IC2") (pin "22") (pinfunction "RD3_22") (pintype "bidirectional"))
    )
    (net (code "74") (name "unconnected-(IC2-RD4-Pad27)") (class "Default")
      (node (ref "IC2") (pin "27") (pinfunction "RD4_27") (pintype "bidirectional"))
    )
    (net (code "75") (name "unconnected-(IC2-RD5-Pad28)") (class "Default")
      (node (ref "IC2") (pin "28") (pinfunction "RD5_28") (pintype "bidirectional"))
    )
    (net (code "76") (name "unconnected-(IC2-RD6-Pad29)") (class "Default")
      (node (ref "IC2") (pin "29") (pinfunction "RD6_29") (pintype "bidirectional"))
    )
    (net (code "77") (name "unconnected-(IC2-RD7-Pad30)") (class "Default")
      (node (ref "IC2") (pin "30") (pinfunction "RD7_30") (pintype "bidirectional"))
    )
    (net (code "78") (name "unconnected-(LCD_Socket-Pad17)") (class "Default")
      (node (ref "LCD_Socket") (pin "17") (pinfunction "17_17") (pintype "passive"))
    )
    (net (code "79") (name "unconnected-(LCD_Socket-Pad18)") (class "Default")
      (node (ref "LCD_Socket") (pin "18") (pinfunction "18_18") (pintype "passive"))
    )
    (net (code "80") (name "unconnected-(LCD_Socket-Pad19)") (class "Default")
      (node (ref "LCD_Socket") (pin "19") (pinfunction "19_19") (pintype "passive"))
    )
    (net (code "81") (name "unconnected-(LCD_Socket-Pad20)") (class "Default")
      (node (ref "LCD_Socket") (pin "20") (pinfunction "20_20") (pintype "passive"))
    )
    (net (code "82") (name "unconnected-(MOD1-Pad1)") (class "Default")
      (node (ref "MOD1") (pin "1") (pinfunction "1_1") (pintype "passive"))
    )
    (net (code "83") (name "unconnected-(MOD1-Pad2)") (class "Default")
      (node (ref "MOD1") (pin "2") (pinfunction "2_2") (pintype "passive"))
    )
    (net (code "84") (name "unconnected-(MOD1-Pad4)") (class "Default")
      (node (ref "MOD1") (pin "4") (pinfunction "4_4") (pintype "passive"))
    )
    (net (code "85") (name "unconnected-(MOD1-Pad5)") (class "Default")
      (node (ref "MOD1") (pin "5") (pinfunction "5_5") (pintype "passive"))
    )
    (net (code "86") (name "unconnected-(MOD1-Pad6)") (class "Default")
      (node (ref "MOD1") (pin "6") (pinfunction "6_6") (pintype "passive"))
    )
    (net (code "87") (name "unconnected-(MOD1-Pad7)") (class "Default")
      (node (ref "MOD1") (pin "7") (pinfunction "7_7") (pintype "passive"))
    )
    (net (code "88") (name "unconnected-(MOD1-Pad8)") (class "Default")
      (node (ref "MOD1") (pin "8") (pinfunction "8_8") (pintype "passive"))
    )
    (net (code "89") (name "unconnected-(MOD1-Pad9)") (class "Default")
      (node (ref "MOD1") (pin "9") (pinfunction "9_9") (pintype "passive"))
    )
    (net (code "90") (name "unconnected-(MOD1-Pad10)") (class "Default")
      (node (ref "MOD1") (pin "10") (pinfunction "10_10") (pintype "passive"))
    )
    (net (code "91") (name "unconnected-(MOD1-Pad11)") (class "Default")
      (node (ref "MOD1") (pin "11") (pinfunction "11_11") (pintype "passive"))
    )
    (net (code "92") (name "unconnected-(SW1-Pad2)") (class "Default")
      (node (ref "SW1") (pin "2") (pinfunction "2_2") (pintype "passive"))
    )
    (net (code "93") (name "unconnected-(SW1-Pad3)") (class "Default")
      (node (ref "SW1") (pin "3") (pinfunction "3_3") (pintype "passive"))
    )
    (net (code "94") (name "unconnected-(SW2-Pad2)") (class "Default")
      (node (ref "SW2") (pin "2") (pinfunction "2_2") (pintype "passive"))
    )
    (net (code "95") (name "unconnected-(SW2-Pad3)") (class "Default")
      (node (ref "SW2") (pin "3") (pinfunction "3_3") (pintype "passive"))
    )
    (net (code "96") (name "unconnected-(SW3-Pad2)") (class "Default")
      (node (ref "SW3") (pin "2") (pinfunction "2_2") (pintype "passive"))
    )
    (net (code "97") (name "unconnected-(SW3-Pad3)") (class "Default")
      (node (ref "SW3") (pin "3") (pinfunction "3_3") (pintype "passive"))
    )
    (net (code "98") (name "unconnected-(SW4-Pad2)") (class "Default")
      (node (ref "SW4") (pin "2") (pinfunction "2_2") (pintype "passive"))
    )
    (net (code "99") (name "unconnected-(SW4-Pad3)") (class "Default")
      (node (ref "SW4") (pin "3") (pinfunction "3_3") (pintype "passive"))
    )
    (net (code "100") (name "unconnected-(SW5-Pad2)") (class "Default")
      (node (ref "SW5") (pin "2") (pinfunction "2_2") (pintype "passive"))
    )
    (net (code "101") (name "unconnected-(SW5-Pad3)") (class "Default")
      (node (ref "SW5") (pin "3") (pinfunction "3_3") (pintype "passive"))
    )
    (net (code "102") (name "unconnected-(SW6-Pad2)") (class "Default")
      (node (ref "SW6") (pin "2") (pinfunction "2_2") (pintype "passive"))
    )
    (net (code "103") (name "unconnected-(SW6-Pad3)") (class "Default")
      (node (ref "SW6") (pin "3") (pinfunction "3_3") (pintype "passive"))
    )
    (net (code "104") (name "unconnected-(SW7-Pad2)") (class "Default")
      (node (ref "SW7") (pin "2") (pinfunction "2_2") (pintype "passive"))
    )
    (net (code "105") (name "unconnected-(SW7-Pad3)") (class "Default")
      (node (ref "SW7") (pin "3") (pinfunction "3_3") (pintype "passive"))
    )
    (net (code "106") (name "unconnected-(SW8-Pad2)") (class "Default")
      (node (ref "SW8") (pin "2") (pinfunction "2_2") (pintype "passive"))
    )
    (net (code "107") (name "unconnected-(SW8-Pad3)") (class "Default")
      (node (ref "SW8") (pin "3") (pinfunction "3_3") (pintype "passive"))
    )
    (net (code "108") (name "unconnected-(SW9-Pad2)") (class "Default")
      (node (ref "SW9") (pin "2") (pinfunction "2_2") (pintype "passive"))
    )
    (net (code "109") (name "unconnected-(SW9-Pad3)") (class "Default")
      (node (ref "SW9") (pin "3") (pinfunction "3_3") (pintype "passive"))
    )
    (net (code "110") (name "unconnected-(TB1-Pad2)") (class "Default")
      (node (ref "TB1") (pin "2") (pinfunction "2_2") (pintype "passive"))
    )
    (net (code "111") (name "unconnected-(TB3-Pad2)") (class "Default")
      (node (ref "TB3") (pin "2") (pinfunction "2_2") (pintype "passive"))
    )
    (net (code "112") (name "unconnected-(TB4-Pad2)") (class "Default")
      (node (ref "TB4") (pin "2") (pinfunction "2_2") (pintype "passive"))
    )
    (net (code "113") (name "unconnected-(TB5-Pad2)") (class "Default")
      (node (ref "TB5") (pin "2") (pinfunction "2_2") (pintype "passive"))
    )
    (net (code "114") (name "unconnected-(TB6-Pad2)") (class "Default")
      (node (ref "TB6") (pin "2") (pinfunction "2_2") (pintype "passive"))
    )
    (net (code "115") (name "unconnected-(TB7-Pad2)") (class "Default")
      (node (ref "TB7") (pin "2") (pinfunction "2_2") (pintype "passive"))
    )
    (net (code "116") (name "unconnected-(TB8-Pad2)") (class "Default")
      (node (ref "TB8") (pin "2") (pinfunction "2_2") (pintype "passive"))
    )
    (net (code "117") (name "unconnected-(TB9-Pad2)") (class "Default")
      (node (ref "TB9") (pin "2") (pinfunction "2_2") (pintype "passive"))
    )
    (net (code "118") (name "unconnected-(TB10-Pad2)") (class "Default")
      (node (ref "TB10") (pin "2") (pinfunction "2_2") (pintype "passive"))
    )
    (net (code "119") (name "unconnected-(TB11-Pad2)") (class "Default")
      (node (ref "TB11") (pin "2") (pinfunction "2_2") (pintype "passive"))
    )
  )
)
